# m_knife.net
KiCad netlist of a schematic drawn in EAGLE
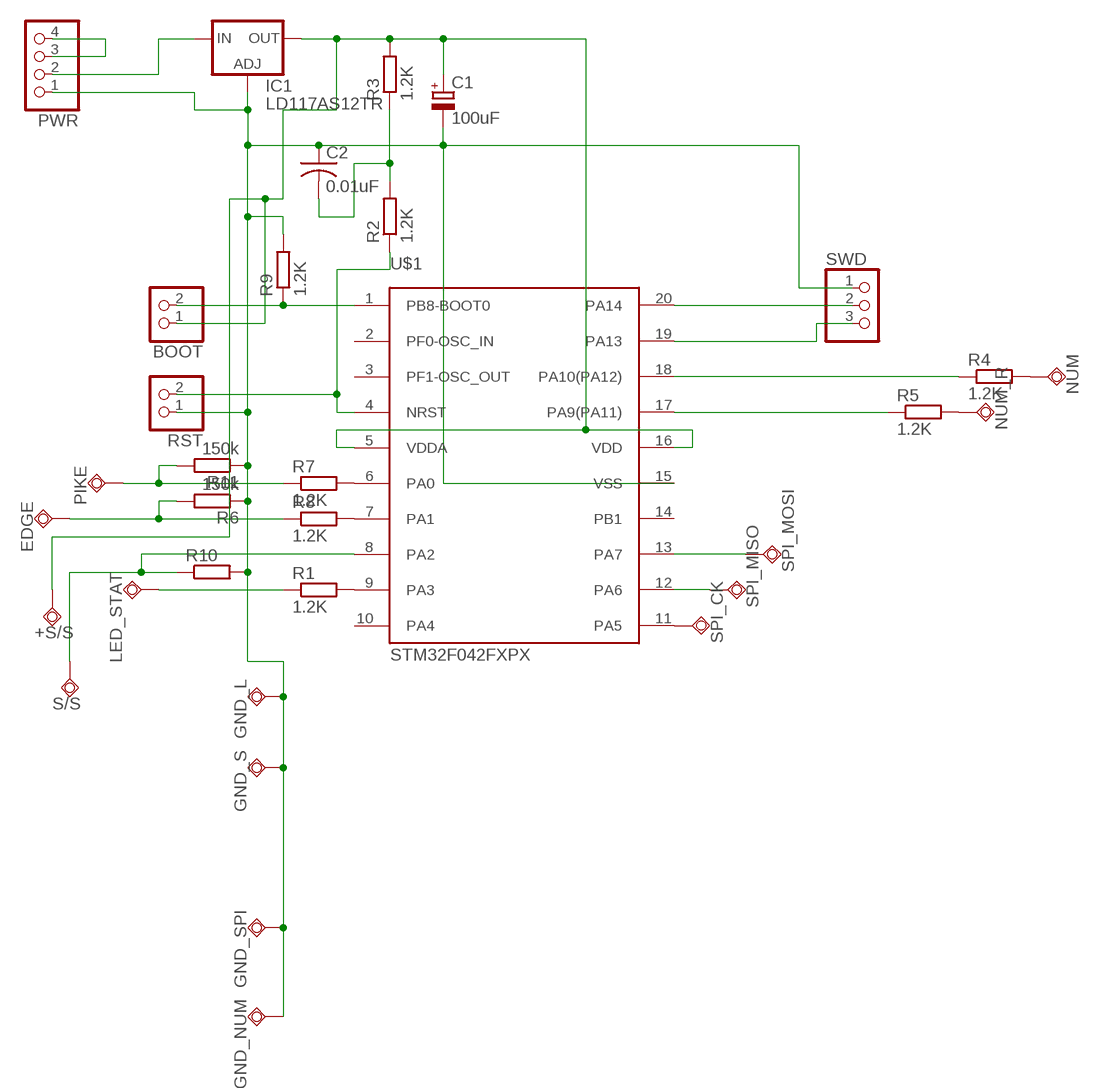
[diagram p0: schematic, sheet 1]

(export (version "E")
  (design (tool "Eeschema 10.0.6"))
  (components
    (comp (ref "+S/S")
      (value "TPSQTP20R")
      (footprint "eagle-import:TP20R")
      (libsource (lib "eagle-import") (part "TPSQTP20R"))
    )
    (comp (ref "BOOT")
      (value "PINHD-1X2")
      (footprint "eagle-import:1X02")
      (libsource (lib "eagle-import") (part "PINHD-1X2"))
    )
    (comp (ref "C1")
      (value "100uF")
      (footprint "eagle-import:SMC_D")
      (libsource (lib "eagle-import") (part "CPOL-EUSMCD"))
    )
    (comp (ref "C2")
      (value "0.01uF")
      (footprint "eagle-import:C1206")
      (libsource (lib "eagle-import") (part "C-USC1206"))
    )
    (comp (ref "EDGE")
      (value "TPSQTP20R")
      (footprint "eagle-import:TP20R")
      (libsource (lib "eagle-import") (part "TPSQTP20R"))
    )
    (comp (ref "GND_L")
      (value "TPSQTP20R")
      (footprint "eagle-import:TP20R")
      (libsource (lib "eagle-import") (part "TPSQTP20R"))
    )
    (comp (ref "GND_NUM")
      (value "TPSQTP20R")
      (footprint "eagle-import:TP20R")
      (libsource (lib "eagle-import") (part "TPSQTP20R"))
    )
    (comp (ref "GND_S")
      (value "TPSQTP20R")
      (footprint "eagle-import:TP20R")
      (libsource (lib "eagle-import") (part "TPSQTP20R"))
    )
    (comp (ref "GND_SPI")
      (value "TPSQTP20R")
      (footprint "eagle-import:TP20R")
      (libsource (lib "eagle-import") (part "TPSQTP20R"))
    )
    (comp (ref "IC1")
      (value "LD117AS12TR")
      (footprint "eagle-import:SOT223")
      (libsource (lib "eagle-import") (part "LD117A?S12TR"))
    )
    (comp (ref "LED_STAT")
      (value "TPSQTP20R")
      (footprint "eagle-import:TP20R")
      (libsource (lib "eagle-import") (part "TPSQTP20R"))
    )
    (comp (ref "NUM")
      (value "TPSQTP20R")
      (footprint "eagle-import:TP20R")
      (libsource (lib "eagle-import") (part "TPSQTP20R"))
    )
    (comp (ref "NUM_R")
      (value "TPSQTP20R")
      (footprint "eagle-import:TP20R")
      (libsource (lib "eagle-import") (part "TPSQTP20R"))
    )
    (comp (ref "PIKE")
      (value "TPSQTP20R")
      (footprint "eagle-import:TP20R")
      (libsource (lib "eagle-import") (part "TPSQTP20R"))
    )
    (comp (ref "PWR")
      (value "PINHD-1X4")
      (footprint "eagle-import:1X04")
      (libsource (lib "eagle-import") (part "PINHD-1X4"))
    )
    (comp (ref "R1")
      (value "1.2K")
      (footprint "eagle-import:R1206")
      (libsource (lib "eagle-import") (part "R-EU_R1206"))
    )
    (comp (ref "R2")
      (value "1.2K")
      (footprint "eagle-import:R1206")
      (libsource (lib "eagle-import") (part "R-EU_R1206"))
    )
    (comp (ref "R3")
      (value "1.2K")
      (footprint "eagle-import:R1206")
      (libsource (lib "eagle-import") (part "R-EU_R1206"))
    )
    (comp (ref "R4")
      (value "1.2K")
      (footprint "eagle-import:R1206")
      (libsource (lib "eagle-import") (part "R-EU_R1206"))
    )
    (comp (ref "R5")
      (value "1.2K")
      (footprint "eagle-import:R1206")
      (libsource (lib "eagle-import") (part "R-EU_R1206"))
    )
    (comp (ref "R6")
      (value "150k")
      (footprint "eagle-import:R1206")
      (libsource (lib "eagle-import") (part "R-EU_R1206"))
    )
    (comp (ref "R7")
      (value "1.2K")
      (footprint "eagle-import:R1206")
      (libsource (lib "eagle-import") (part "R-EU_R1206"))
    )
    (comp (ref "R8")
      (value "1.2K")
      (footprint "eagle-import:R1206")
      (libsource (lib "eagle-import") (part "R-EU_R1206"))
    )
    (comp (ref "R9")
      (value "1.2K")
      (footprint "eagle-import:R1206")
      (libsource (lib "eagle-import") (part "R-EU_R1206"))
    )
    (comp (ref "R10")
      (value "R-EU_R1206")
      (footprint "eagle-import:R1206")
      (libsource (lib "eagle-import") (part "R-EU_R1206"))
    )
    (comp (ref "R11")
      (value "150k")
      (footprint "eagle-import:R1206")
      (libsource (lib "eagle-import") (part "R-EU_R1206"))
    )
    (comp (ref "RST")
      (value "PINHD-1X2")
      (footprint "eagle-import:1X02")
      (libsource (lib "eagle-import") (part "PINHD-1X2"))
    )
    (comp (ref "S/S")
      (value "TPSQTP20R")
      (footprint "eagle-import:TP20R")
      (libsource (lib "eagle-import") (part "TPSQTP20R"))
    )
    (comp (ref "SPI_CK")
      (value "TPSQTP20R")
      (footprint "eagle-import:TP20R")
      (libsource (lib "eagle-import") (part "TPSQTP20R"))
    )
    (comp (ref "SPI_MISO")
      (value "TPSQTP20R")
      (footprint "eagle-import:TP20R")
      (libsource (lib "eagle-import") (part "TPSQTP20R"))
    )
    (comp (ref "SPI_MOSI")
      (value "TPSQTP20R")
      (footprint "eagle-import:TP20R")
      (libsource (lib "eagle-import") (part "TPSQTP20R"))
    )
    (comp (ref "SWD")
      (value "PINHD-1X3")
      (footprint "eagle-import:1X03")
      (libsource (lib "eagle-import") (part "PINHD-1X3"))
    )
    (comp (ref "U$1")
      (value "STM32F042FXPX")
      (footprint "eagle-import:TSSOP20")
      (libsource (lib "eagle-import") (part "STM32F042FXPX"))
    )
  )
  (nets
    (net (code "1") (name "Net-(C2-Pad2)") (class "Default")
      (node (ref "C2") (pin "2") (pinfunction "2_2") (pintype "passive"))
      (node (ref "R2") (pin "2") (pinfunction "2_2") (pintype "passive"))
      (node (ref "R3") (pin "1") (pinfunction "1_1") (pintype "passive"))
    )
    (net (code "2") (name "Net-(EDGE-PadTP)") (class "Default")
      (node (ref "EDGE") (pin "TP") (pinfunction "TP_TP") (pintype "input"))
      (node (ref "R6") (pin "2") (pinfunction "2_2") (pintype "passive"))
      (node (ref "R8") (pin "1") (pinfunction "1_1") (pintype "passive"))
    )
    (net (code "3") (name "Net-(IC1-ADJ)") (class "Default")
      (node (ref "C1") (pin "-") (pinfunction "-_-") (pintype "passive"))
      (node (ref "C2") (pin "1") (pinfunction "1_1") (pintype "passive"))
      (node (ref "GND_L") (pin "TP") (pinfunction "TP_TP") (pintype "input"))
      (node (ref "GND_NUM") (pin "TP") (pinfunction "TP_TP") (pintype "input"))
      (node (ref "GND_S") (pin "TP") (pinfunction "TP_TP") (pintype "input"))
      (node (ref "GND_SPI") (pin "TP") (pinfunction "TP_TP") (pintype "input"))
      (node (ref "IC1") (pin "1") (pinfunction "ADJ_1") (pintype "input"))
      (node (ref "PWR") (pin "1") (pinfunction "1_1") (pintype "passive"))
      (node (ref "R10") (pin "2") (pinfunction "2_2") (pintype "passive"))
      (node (ref "R11") (pin "1") (pinfunction "1_1") (pintype "passive"))
      (node (ref "R6") (pin "1") (pinfunction "1_1") (pintype "passive"))
      (node (ref "R9") (pin "2") (pinfunction "2_2") (pintype "passive"))
      (node (ref "RST") (pin "1") (pinfunction "1_1") (pintype "passive"))
      (node (ref "SWD") (pin "1") (pinfunction "1_1") (pintype "passive"))
      (node (ref "U$1") (pin "15") (pinfunction "VSS_15") (pintype "bidirectional"))
    )
    (net (code "4") (name "Net-(IC1-IN)") (class "Default")
      (node (ref "IC1") (pin "3") (pinfunction "IN_3") (pintype "input"))
      (node (ref "PWR") (pin "2") (pinfunction "2_2") (pintype "passive"))
    )
    (net (code "5") (name "Net-(IC1-OUT)") (class "Default")
      (node (ref "+S/S") (pin "TP") (pinfunction "TP_TP") (pintype "input"))
      (node (ref "BOOT") (pin "1") (pinfunction "1_1") (pintype "passive"))
      (node (ref "C1") (pin "+") (pinfunction "+_+") (pintype "passive"))
      (node (ref "IC1") (pin "4") (pinfunction "OUT_4") (pintype "passive"))
      (node (ref "R3") (pin "2") (pinfunction "2_2") (pintype "passive"))
      (node (ref "U$1") (pin "16") (pinfunction "VDD_16") (pintype "bidirectional"))
      (node (ref "U$1") (pin "5") (pinfunction "VDDA_5") (pintype "bidirectional"))
    )
    (net (code "6") (name "Net-(LED_STAT-PadTP)") (class "Default")
      (node (ref "LED_STAT") (pin "TP") (pinfunction "TP_TP") (pintype "input"))
      (node (ref "R1") (pin "1") (pinfunction "1_1") (pintype "passive"))
    )
    (net (code "7") (name "Net-(NUM-PadTP)") (class "Default")
      (node (ref "NUM") (pin "TP") (pinfunction "TP_TP") (pintype "input"))
      (node (ref "R4") (pin "2") (pinfunction "2_2") (pintype "passive"))
    )
    (net (code "8") (name "Net-(NUM_R-PadTP)") (class "Default")
      (node (ref "NUM_R") (pin "TP") (pinfunction "TP_TP") (pintype "input"))
      (node (ref "R5") (pin "2") (pinfunction "2_2") (pintype "passive"))
    )
    (net (code "9") (name "Net-(PIKE-PadTP)") (class "Default")
      (node (ref "PIKE") (pin "TP") (pinfunction "TP_TP") (pintype "input"))
      (node (ref "R11") (pin "2") (pinfunction "2_2") (pintype "passive"))
      (node (ref "R7") (pin "1") (pinfunction "1_1") (pintype "passive"))
    )
    (net (code "10") (name "Net-(PWR-Pad3)") (class "Default")
      (node (ref "PWR") (pin "3") (pinfunction "3_3") (pintype "passive"))
      (node (ref "PWR") (pin "4") (pinfunction "4_4") (pintype "passive"))
    )
    (net (code "11") (name "Net-(U$1-NRST)") (class "Default")
      (node (ref "R2") (pin "1") (pinfunction "1_1") (pintype "passive"))
      (node (ref "RST") (pin "2") (pinfunction "2_2") (pintype "passive"))
      (node (ref "U$1") (pin "4") (pinfunction "NRST_4") (pintype "bidirectional"))
    )
    (net (code "12") (name "Net-(U$1-PA0)") (class "Default")
      (node (ref "R7") (pin "2") (pinfunction "2_2") (pintype "passive"))
      (node (ref "U$1") (pin "6") (pinfunction "PA0_6") (pintype "bidirectional"))
    )
    (net (code "13") (name "Net-(U$1-PA1)") (class "Default")
      (node (ref "R8") (pin "2") (pinfunction "2_2") (pintype "passive"))
      (node (ref "U$1") (pin "7") (pinfunction "PA1_7") (pintype "bidirectional"))
    )
    (net (code "14") (name "Net-(U$1-PA2)") (class "Default")
      (node (ref "R10") (pin "1") (pinfunction "1_1") (pintype "passive"))
      (node (ref "S/S") (pin "TP") (pinfunction "TP_TP") (pintype "input"))
      (node (ref "U$1") (pin "8") (pinfunction "PA2_8") (pintype "bidirectional"))
    )
    (net (code "15") (name "Net-(U$1-PA3)") (class "Default")
      (node (ref "R1") (pin "2") (pinfunction "2_2") (pintype "passive"))
      (node (ref "U$1") (pin "9") (pinfunction "PA3_9") (pintype "bidirectional"))
    )
    (net (code "16") (name "Net-(U$1-PA5)") (class "Default")
      (node (ref "SPI_CK") (pin "TP") (pinfunction "TP_TP") (pintype "input"))
      (node (ref "U$1") (pin "11") (pinfunction "PA5_11") (pintype "bidirectional"))
    )
    (net (code "17") (name "Net-(U$1-PA6)") (class "Default")
      (node (ref "SPI_MISO") (pin "TP") (pinfunction "TP_TP") (pintype "input"))
      (node (ref "U$1") (pin "12") (pinfunction "PA6_12") (pintype "bidirectional"))
    )
    (net (code "18") (name "Net-(U$1-PA7)") (class "Default")
      (node (ref "SPI_MOSI") (pin "TP") (pinfunction "TP_TP") (pintype "input"))
      (node (ref "U$1") (pin "13") (pinfunction "PA7_13") (pintype "bidirectional"))
    )
    (net (code "19") (name "Net-(U$1-PA9(PA11))") (class "Default")
      (node (ref "R5") (pin "1") (pinfunction "1_1") (pintype "passive"))
      (node (ref "U$1") (pin "17") (pinfunction "PA9(PA11)_17") (pintype "bidirectional"))
    )
    (net (code "20") (name "Net-(U$1-PA10(PA12))") (class "Default")
      (node (ref "R4") (pin "1") (pinfunction "1_1") (pintype "passive"))
      (node (ref "U$1") (pin "18") (pinfunction "PA10(PA12)_18") (pintype "bidirectional"))
    )
    (net (code "21") (name "Net-(U$1-PA13)") (class "Default")
      (node (ref "SWD") (pin "3") (pinfunction "3_3") (pintype "passive"))
      (node (ref "U$1") (pin "19") (pinfunction "PA13_19") (pintype "bidirectional"))
    )
    (net (code "22") (name "Net-(U$1-PA14)") (class "Default")
      (node (ref "SWD") (pin "2") (pinfunction "2_2") (pintype "passive"))
      (node (ref "U$1") (pin "20") (pinfunction "PA14_20") (pintype "bidirectional"))
    )
    (net (code "23") (name "Net-(U$1-PB8-BOOT0)") (class "Default")
      (node (ref "BOOT") (pin "2") (pinfunction "2_2") (pintype "passive"))
      (node (ref "R9") (pin "1") (pinfunction "1_1") (pintype "passive"))
      (node (ref "U$1") (pin "1") (pinfunction "PB8-BOOT0_1") (pintype "bidirectional"))
    )
    (net (code "24") (name "unconnected-(U$1-PA4-Pad10)") (class "Default")
      (node (ref "U$1") (pin "10") (pinfunction "PA4_10") (pintype "bidirectional"))
    )
    (net (code "25") (name "unconnected-(U$1-PB1-Pad14)") (class "Default")
      (node (ref "U$1") (pin "14") (pinfunction "PB1_14") (pintype "bidirectional"))
    )
    (net (code "26") (name "unconnected-(U$1-PF0-OSC_IN-Pad2)") (class "Default")
      (node (ref "U$1") (pin "2") (pinfunction "PF0-OSC_IN_2") (pintype "bidirectional"))
    )
    (net (code "27") (name "unconnected-(U$1-PF1-OSC_OUT-Pad3)") (class "Default")
      (node (ref "U$1") (pin "3") (pinfunction "PF1-OSC_OUT_3") (pintype "bidirectional"))
    )
  )
)
